# hall_sensor.net
KiCad netlist of a schematic drawn in EAGLE
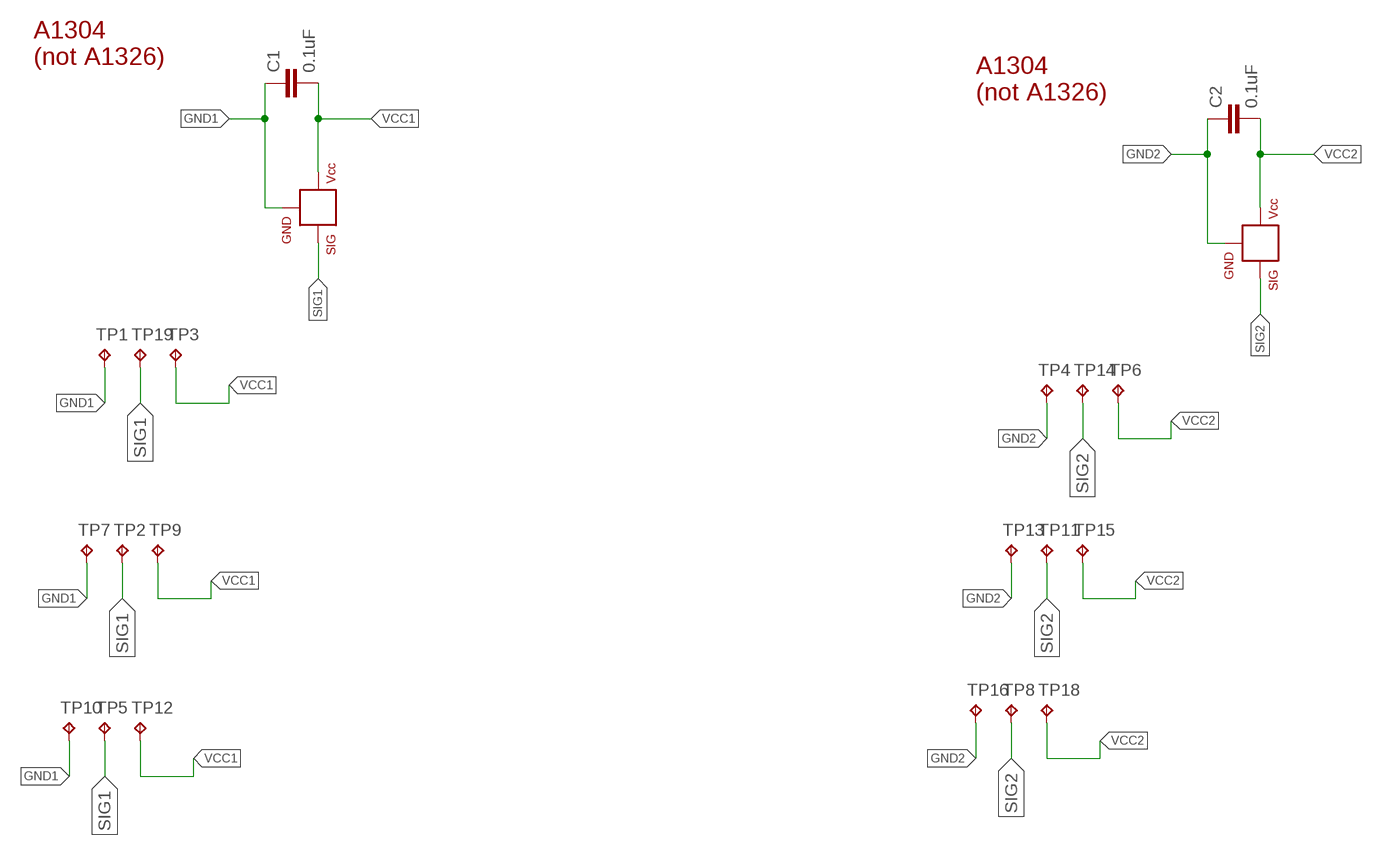
[diagram p0: schematic, sheet 1]

(export (version "E")
  (design (tool "Eeschema 10.0.6"))
  (components
    (comp (ref "C1")
      (value "0.1uF")
      (footprint "eagle-import:0603-CAP")
      (libsource (lib "eagle-import") (part "CAP0603-CAP"))
    )
    (comp (ref "C2")
      (value "0.1uF")
      (footprint "eagle-import:0603-CAP")
      (libsource (lib "eagle-import") (part "CAP0603-CAP"))
    )
    (comp (ref "HALL")
      (value "HALLEFFECT-A1326")
      (footprint "eagle-import:SOT23-3")
      (libsource (lib "eagle-import") (part "HALLEFFECT-A1326"))
    )
    (comp (ref "HALL1")
      (value "HALLEFFECT-A1326")
      (footprint "eagle-import:SOT23-3")
      (libsource (lib "eagle-import") (part "HALLEFFECT-A1326"))
    )
    (comp (ref "TP1")
      (value "TPTP10SQ")
      (footprint "eagle-import:TP10SQ")
      (libsource (lib "eagle-import") (part "TPTP10SQ"))
    )
    (comp (ref "TP2")
      (value "TPTP15R")
      (footprint "eagle-import:TP15R")
      (libsource (lib "eagle-import") (part "TPTP15R"))
    )
    (comp (ref "TP3")
      (value "TPTP10SQ")
      (footprint "eagle-import:TP10SQ")
      (libsource (lib "eagle-import") (part "TPTP10SQ"))
    )
    (comp (ref "TP4")
      (value "TPTP10SQ")
      (footprint "eagle-import:TP10SQ")
      (libsource (lib "eagle-import") (part "TPTP10SQ"))
    )
    (comp (ref "TP5")
      (value "TPTP15R")
      (footprint "eagle-import:TP15R")
      (libsource (lib "eagle-import") (part "TPTP15R"))
    )
    (comp (ref "TP6")
      (value "TPTP10SQ")
      (footprint "eagle-import:TP10SQ")
      (libsource (lib "eagle-import") (part "TPTP10SQ"))
    )
    (comp (ref "TP7")
      (value "TPTP10SQ")
      (footprint "eagle-import:TP10SQ")
      (libsource (lib "eagle-import") (part "TPTP10SQ"))
    )
    (comp (ref "TP8")
      (value "TPTP15R")
      (footprint "eagle-import:TP15R")
      (libsource (lib "eagle-import") (part "TPTP15R"))
    )
    (comp (ref "TP9")
      (value "TPTP10SQ")
      (footprint "eagle-import:TP10SQ")
      (libsource (lib "eagle-import") (part "TPTP10SQ"))
    )
    (comp (ref "TP10")
      (value "TPTP10SQ")
      (footprint "eagle-import:TP10SQ")
      (libsource (lib "eagle-import") (part "TPTP10SQ"))
    )
    (comp (ref "TP11")
      (value "TPTP15R")
      (footprint "eagle-import:TP15R")
      (libsource (lib "eagle-import") (part "TPTP15R"))
    )
    (comp (ref "TP12")
      (value "TPTP10SQ")
      (footprint "eagle-import:TP10SQ")
      (libsource (lib "eagle-import") (part "TPTP10SQ"))
    )
    (comp (ref "TP13")
      (value "TPTP10SQ")
      (footprint "eagle-import:TP10SQ")
      (libsource (lib "eagle-import") (part "TPTP10SQ"))
    )
    (comp (ref "TP14")
      (value "TPTP15R")
      (footprint "eagle-import:TP15R")
      (libsource (lib "eagle-import") (part "TPTP15R"))
    )
    (comp (ref "TP15")
      (value "TPTP10SQ")
      (footprint "eagle-import:TP10SQ")
      (libsource (lib "eagle-import") (part "TPTP10SQ"))
    )
    (comp (ref "TP16")
      (value "TPTP10SQ")
      (footprint "eagle-import:TP10SQ")
      (libsource (lib "eagle-import") (part "TPTP10SQ"))
    )
    (comp (ref "TP18")
      (value "TPTP10SQ")
      (footprint "eagle-import:TP10SQ")
      (libsource (lib "eagle-import") (part "TPTP10SQ"))
    )
    (comp (ref "TP19")
      (value "TPTP15R")
      (footprint "eagle-import:TP15R")
      (libsource (lib "eagle-import") (part "TPTP15R"))
    )
  )
  (nets
    (net (code "1") (name "GND1") (class "Default")
      (node (ref "C1") (pin "1") (pinfunction "1_1") (pintype "passive"))
      (node (ref "HALL") (pin "3") (pinfunction "GND_3") (pintype "bidirectional"))
      (node (ref "TP1") (pin "TP") (pinfunction "TP_TP") (pintype "input"))
      (node (ref "TP10") (pin "TP") (pinfunction "TP_TP") (pintype "input"))
      (node (ref "TP7") (pin "TP") (pinfunction "TP_TP") (pintype "input"))
    )
    (net (code "2") (name "GND2") (class "Default")
      (node (ref "C2") (pin "1") (pinfunction "1_1") (pintype "passive"))
      (node (ref "HALL1") (pin "3") (pinfunction "GND_3") (pintype "bidirectional"))
      (node (ref "TP13") (pin "TP") (pinfunction "TP_TP") (pintype "input"))
      (node (ref "TP16") (pin "TP") (pinfunction "TP_TP") (pintype "input"))
      (node (ref "TP4") (pin "TP") (pinfunction "TP_TP") (pintype "input"))
    )
    (net (code "3") (name "SIG1") (class "Default")
      (node (ref "HALL") (pin "2") (pinfunction "SIG_2") (pintype "bidirectional"))
      (node (ref "TP19") (pin "TP") (pinfunction "TP_TP") (pintype "input"))
      (node (ref "TP2") (pin "TP") (pinfunction "TP_TP") (pintype "input"))
      (node (ref "TP5") (pin "TP") (pinfunction "TP_TP") (pintype "input"))
    )
    (net (code "4") (name "SIG2") (class "Default")
      (node (ref "HALL1") (pin "2") (pinfunction "SIG_2") (pintype "bidirectional"))
      (node (ref "TP11") (pin "TP") (pinfunction "TP_TP") (pintype "input"))
      (node (ref "TP14") (pin "TP") (pinfunction "TP_TP") (pintype "input"))
      (node (ref "TP8") (pin "TP") (pinfunction "TP_TP") (pintype "input"))
    )
    (net (code "5") (name "VCC1") (class "Default")
      (node (ref "C1") (pin "2") (pinfunction "2_2") (pintype "passive"))
      (node (ref "HALL") (pin "1") (pinfunction "VCC_1") (pintype "bidirectional"))
      (node (ref "TP12") (pin "TP") (pinfunction "TP_TP") (pintype "input"))
      (node (ref "TP3") (pin "TP") (pinfunction "TP_TP") (pintype "input"))
      (node (ref "TP9") (pin "TP") (pinfunction "TP_TP") (pintype "input"))
    )
    (net (code "6") (name "VCC2") (class "Default")
      (node (ref "C2") (pin "2") (pinfunction "2_2") (pintype "passive"))
      (node (ref "HALL1") (pin "1") (pinfunction "VCC_1") (pintype "bidirectional"))
      (node (ref "TP15") (pin "TP") (pinfunction "TP_TP") (pintype "input"))
      (node (ref "TP18") (pin "TP") (pinfunction "TP_TP") (pintype "input"))
      (node (ref "TP6") (pin "TP") (pinfunction "TP_TP") (pintype "input"))
    )
  )
)
